# simpler_dj_midi_controlle.net
KiCad netlist of a schematic drawn in EAGLE
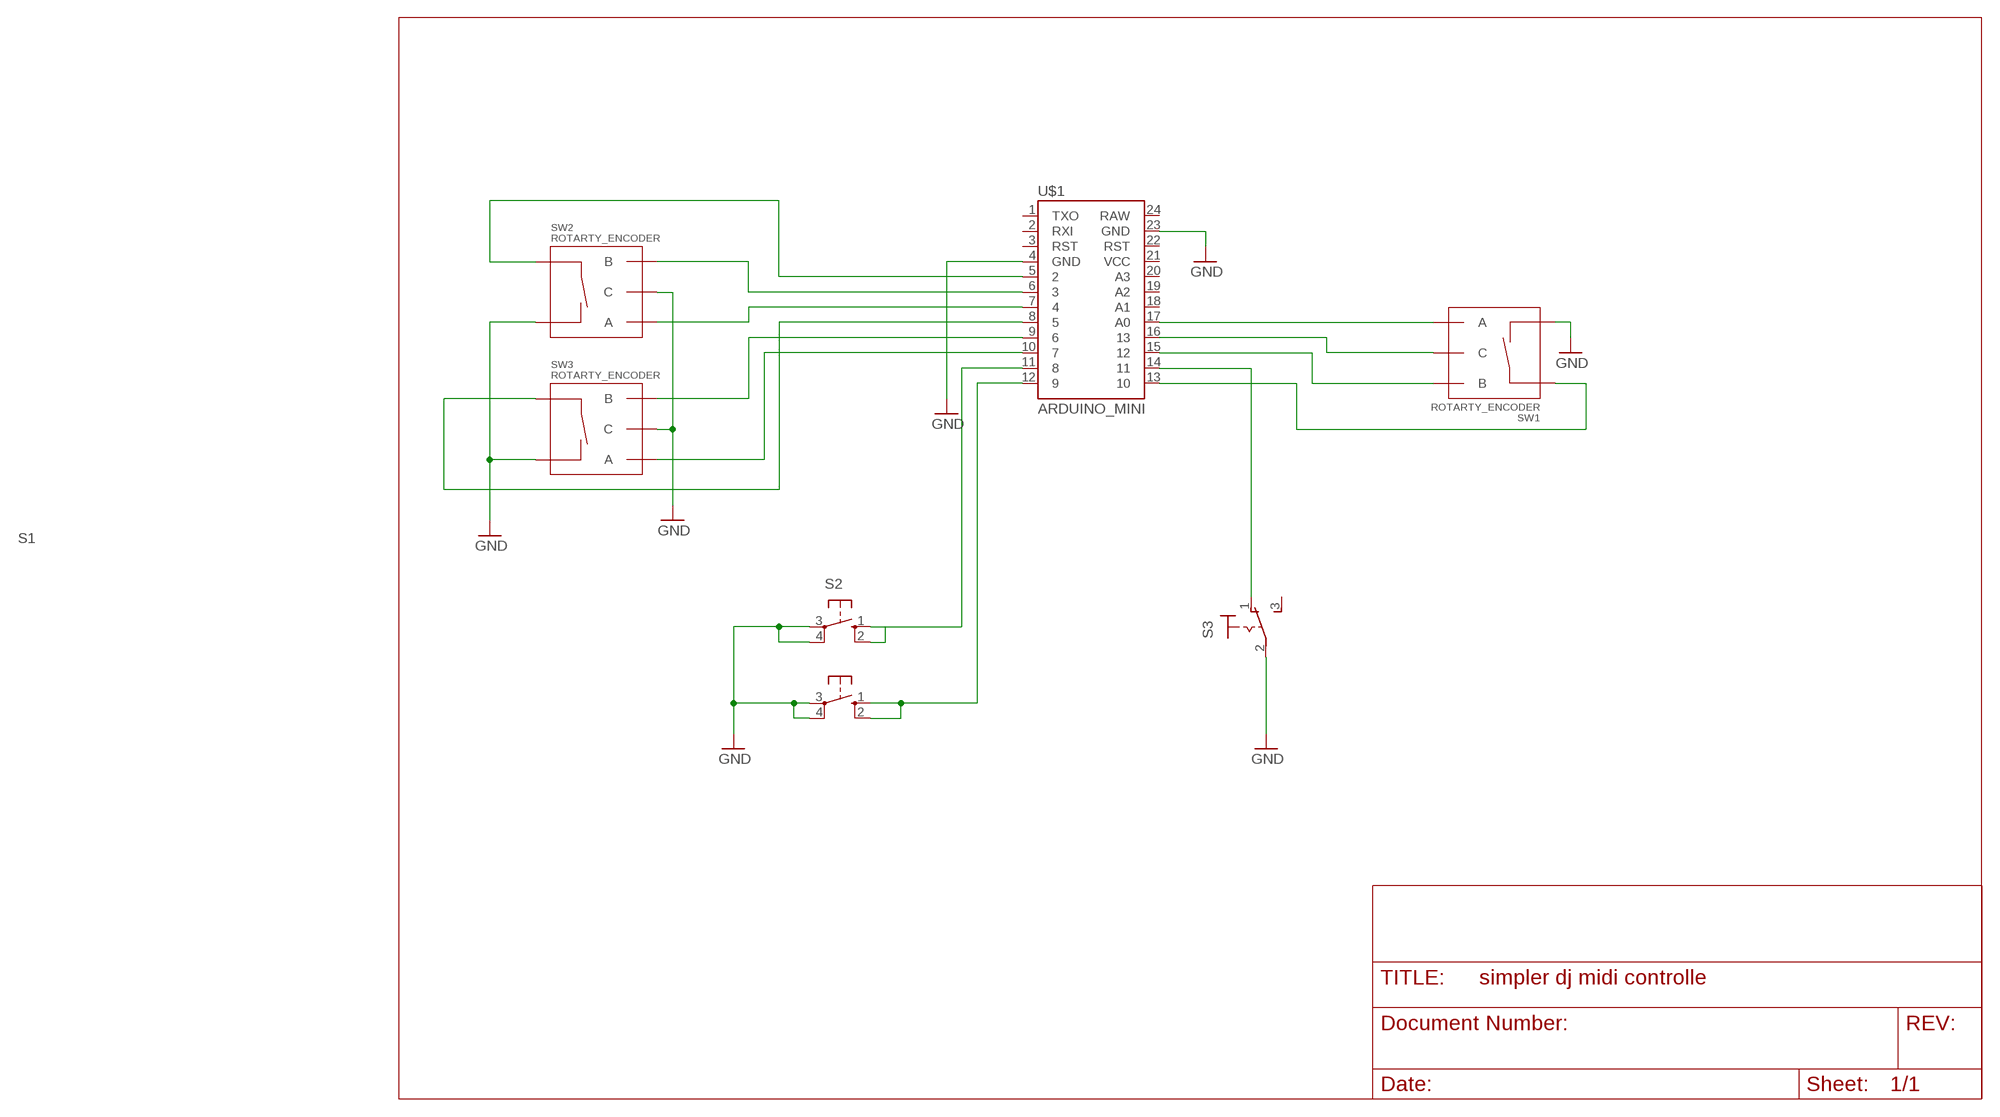
[diagram p0: schematic, sheet 1]

(export (version "E")
  (design (tool "Eeschema 10.0.6"))
  (components
    (comp (ref "S1")
      (value "10-XX")
      (footprint "eagle-import:B3F-10XX")
      (fields (field (name "MPN") "B3F-1000"))
      (libsource (lib "eagle-import") (part "10-XX"))
    )
    (comp (ref "S2")
      (value "10-XX")
      (footprint "eagle-import:B3F-10XX")
      (fields (field (name "MPN") "B3F-1000"))
      (libsource (lib "eagle-import") (part "10-XX"))
    )
    (comp (ref "S3")
      (value "320-916")
      (footprint "eagle-import:320-916")
      (libsource (lib "eagle-import") (part "320-916"))
    )
    (comp (ref "SW1")
      (value "ROTARTY_ENCODER")
      (footprint "eagle-import:ROTARY_ENC_PLAIN")
      (libsource (lib "eagle-import") (part "ROTARTY_ENCODER"))
    )
    (comp (ref "SW2")
      (value "ROTARTY_ENCODER")
      (footprint "eagle-import:ROTARY_ENC_PLAIN")
      (libsource (lib "eagle-import") (part "ROTARTY_ENCODER"))
    )
    (comp (ref "SW3")
      (value "ROTARTY_ENCODER")
      (footprint "eagle-import:ROTARY_ENC_PLAIN")
      (libsource (lib "eagle-import") (part "ROTARTY_ENCODER"))
    )
    (comp (ref "U$1")
      (value "ARDUINO_MINI")
      (footprint "eagle-import:ARDUINO_MINI")
      (libsource (lib "eagle-import") (part "ARDUINO_MINI"))
    )
  )
  (nets
    (net (code "1") (name "GND") (class "Default")
      (node (ref "S1") (pin "3") (pinfunction "P_3") (pintype "passive"))
      (node (ref "S1") (pin "4") (pinfunction "P1_4") (pintype "passive"))
      (node (ref "S2") (pin "3") (pinfunction "P_3") (pintype "passive"))
      (node (ref "S2") (pin "4") (pinfunction "P1_4") (pintype "passive"))
      (node (ref "S3") (pin "2") (pinfunction "P_2") (pintype "passive"))
      (node (ref "SW1") (pin "SW-") (pinfunction "SW-_SW-") (pintype "bidirectional"))
      (node (ref "SW2") (pin "C") (pinfunction "C_C") (pintype "bidirectional"))
      (node (ref "SW2") (pin "SW-") (pinfunction "SW-_SW-") (pintype "bidirectional"))
      (node (ref "SW3") (pin "C") (pinfunction "C_C") (pintype "bidirectional"))
      (node (ref "SW3") (pin "SW-") (pinfunction "SW-_SW-") (pintype "bidirectional"))
      (node (ref "U$1") (pin "23") (pinfunction "GND_23") (pintype "bidirectional"))
      (node (ref "U$1") (pin "4") (pinfunction "GND_4") (pintype "bidirectional"))
    )
    (net (code "2") (name "Net-(S1-S)") (class "Default")
      (node (ref "S1") (pin "1") (pinfunction "S_1") (pintype "passive"))
      (node (ref "S1") (pin "2") (pinfunction "S1_2") (pintype "passive"))
      (node (ref "U$1") (pin "12") (pinfunction "9_12") (pintype "bidirectional"))
    )
    (net (code "3") (name "Net-(S2-S)") (class "Default")
      (node (ref "S2") (pin "1") (pinfunction "S_1") (pintype "passive"))
      (node (ref "S2") (pin "2") (pinfunction "S1_2") (pintype "passive"))
      (node (ref "U$1") (pin "11") (pinfunction "8_11") (pintype "bidirectional"))
    )
    (net (code "4") (name "Net-(S3-O)") (class "Default")
      (node (ref "S3") (pin "1") (pinfunction "O_1") (pintype "passive"))
      (node (ref "U$1") (pin "14") (pinfunction "11_14") (pintype "bidirectional"))
    )
    (net (code "5") (name "Net-(U$1-2)") (class "Default")
      (node (ref "SW2") (pin "SW+") (pinfunction "SW+_SW+") (pintype "bidirectional"))
      (node (ref "U$1") (pin "5") (pinfunction "2_5") (pintype "bidirectional"))
    )
    (net (code "6") (name "Net-(U$1-3)") (class "Default")
      (node (ref "SW2") (pin "B") (pinfunction "B_B") (pintype "bidirectional"))
      (node (ref "U$1") (pin "6") (pinfunction "3_6") (pintype "bidirectional"))
    )
    (net (code "7") (name "Net-(U$1-4)") (class "Default")
      (node (ref "SW2") (pin "A") (pinfunction "A_A") (pintype "bidirectional"))
      (node (ref "U$1") (pin "7") (pinfunction "4_7") (pintype "bidirectional"))
    )
    (net (code "8") (name "Net-(U$1-5)") (class "Default")
      (node (ref "SW3") (pin "SW+") (pinfunction "SW+_SW+") (pintype "bidirectional"))
      (node (ref "U$1") (pin "8") (pinfunction "5_8") (pintype "bidirectional"))
    )
    (net (code "9") (name "Net-(U$1-6)") (class "Default")
      (node (ref "SW3") (pin "B") (pinfunction "B_B") (pintype "bidirectional"))
      (node (ref "U$1") (pin "9") (pinfunction "6_9") (pintype "bidirectional"))
    )
    (net (code "10") (name "Net-(U$1-7)") (class "Default")
      (node (ref "SW3") (pin "A") (pinfunction "A_A") (pintype "bidirectional"))
      (node (ref "U$1") (pin "10") (pinfunction "7_10") (pintype "bidirectional"))
    )
    (net (code "11") (name "Net-(U$1-10)") (class "Default")
      (node (ref "SW1") (pin "SW+") (pinfunction "SW+_SW+") (pintype "bidirectional"))
      (node (ref "U$1") (pin "13") (pinfunction "10_13") (pintype "bidirectional"))
    )
    (net (code "12") (name "Net-(U$1-12)") (class "Default")
      (node (ref "SW1") (pin "B") (pinfunction "B_B") (pintype "bidirectional"))
      (node (ref "U$1") (pin "15") (pinfunction "12_15") (pintype "bidirectional"))
    )
    (net (code "13") (name "Net-(U$1-13)") (class "Default")
      (node (ref "SW1") (pin "C") (pinfunction "C_C") (pintype "bidirectional"))
      (node (ref "U$1") (pin "16") (pinfunction "13_16") (pintype "bidirectional"))
    )
    (net (code "14") (name "Net-(U$1-A0)") (class "Default")
      (node (ref "SW1") (pin "A") (pinfunction "A_A") (pintype "bidirectional"))
      (node (ref "U$1") (pin "17") (pinfunction "A0_17") (pintype "bidirectional"))
    )
    (net (code "15") (name "unconnected-(S3-S-Pad3)") (class "Default")
      (node (ref "S3") (pin "3") (pinfunction "S_3") (pintype "passive"))
    )
    (net (code "16") (name "unconnected-(U$1-A1-Pad18)") (class "Default")
      (node (ref "U$1") (pin "18") (pinfunction "A1_18") (pintype "bidirectional"))
    )
    (net (code "17") (name "unconnected-(U$1-A2-Pad19)") (class "Default")
      (node (ref "U$1") (pin "19") (pinfunction "A2_19") (pintype "bidirectional"))
    )
    (net (code "18") (name "unconnected-(U$1-A3-Pad20)") (class "Default")
      (node (ref "U$1") (pin "20") (pinfunction "A3_20") (pintype "bidirectional"))
    )
    (net (code "19") (name "unconnected-(U$1-RAW-Pad24)") (class "Default")
      (node (ref "U$1") (pin "24") (pinfunction "RAW_24") (pintype "bidirectional"))
    )
    (net (code "20") (name "unconnected-(U$1-RST-Pad3)") (class "Default")
      (node (ref "U$1") (pin "3") (pinfunction "RST_3") (pintype "bidirectional"))
    )
    (net (code "21") (name "unconnected-(U$1-RST-Pad22)") (class "Default")
      (node (ref "U$1") (pin "22") (pinfunction "RST_22") (pintype "bidirectional"))
    )
    (net (code "22") (name "unconnected-(U$1-RXI-Pad2)") (class "Default")
      (node (ref "U$1") (pin "2") (pinfunction "RXI_2") (pintype "bidirectional"))
    )
    (net (code "23") (name "unconnected-(U$1-TXO-Pad1)") (class "Default")
      (node (ref "U$1") (pin "1") (pinfunction "TXO_1") (pintype "bidirectional"))
    )
    (net (code "24") (name "unconnected-(U$1-VCC-Pad21)") (class "Default")
      (node (ref "U$1") (pin "21") (pinfunction "VCC_21") (pintype "bidirectional"))
    )
  )
)
